# groundStation.net
KiCad netlist of a schematic drawn in EAGLE
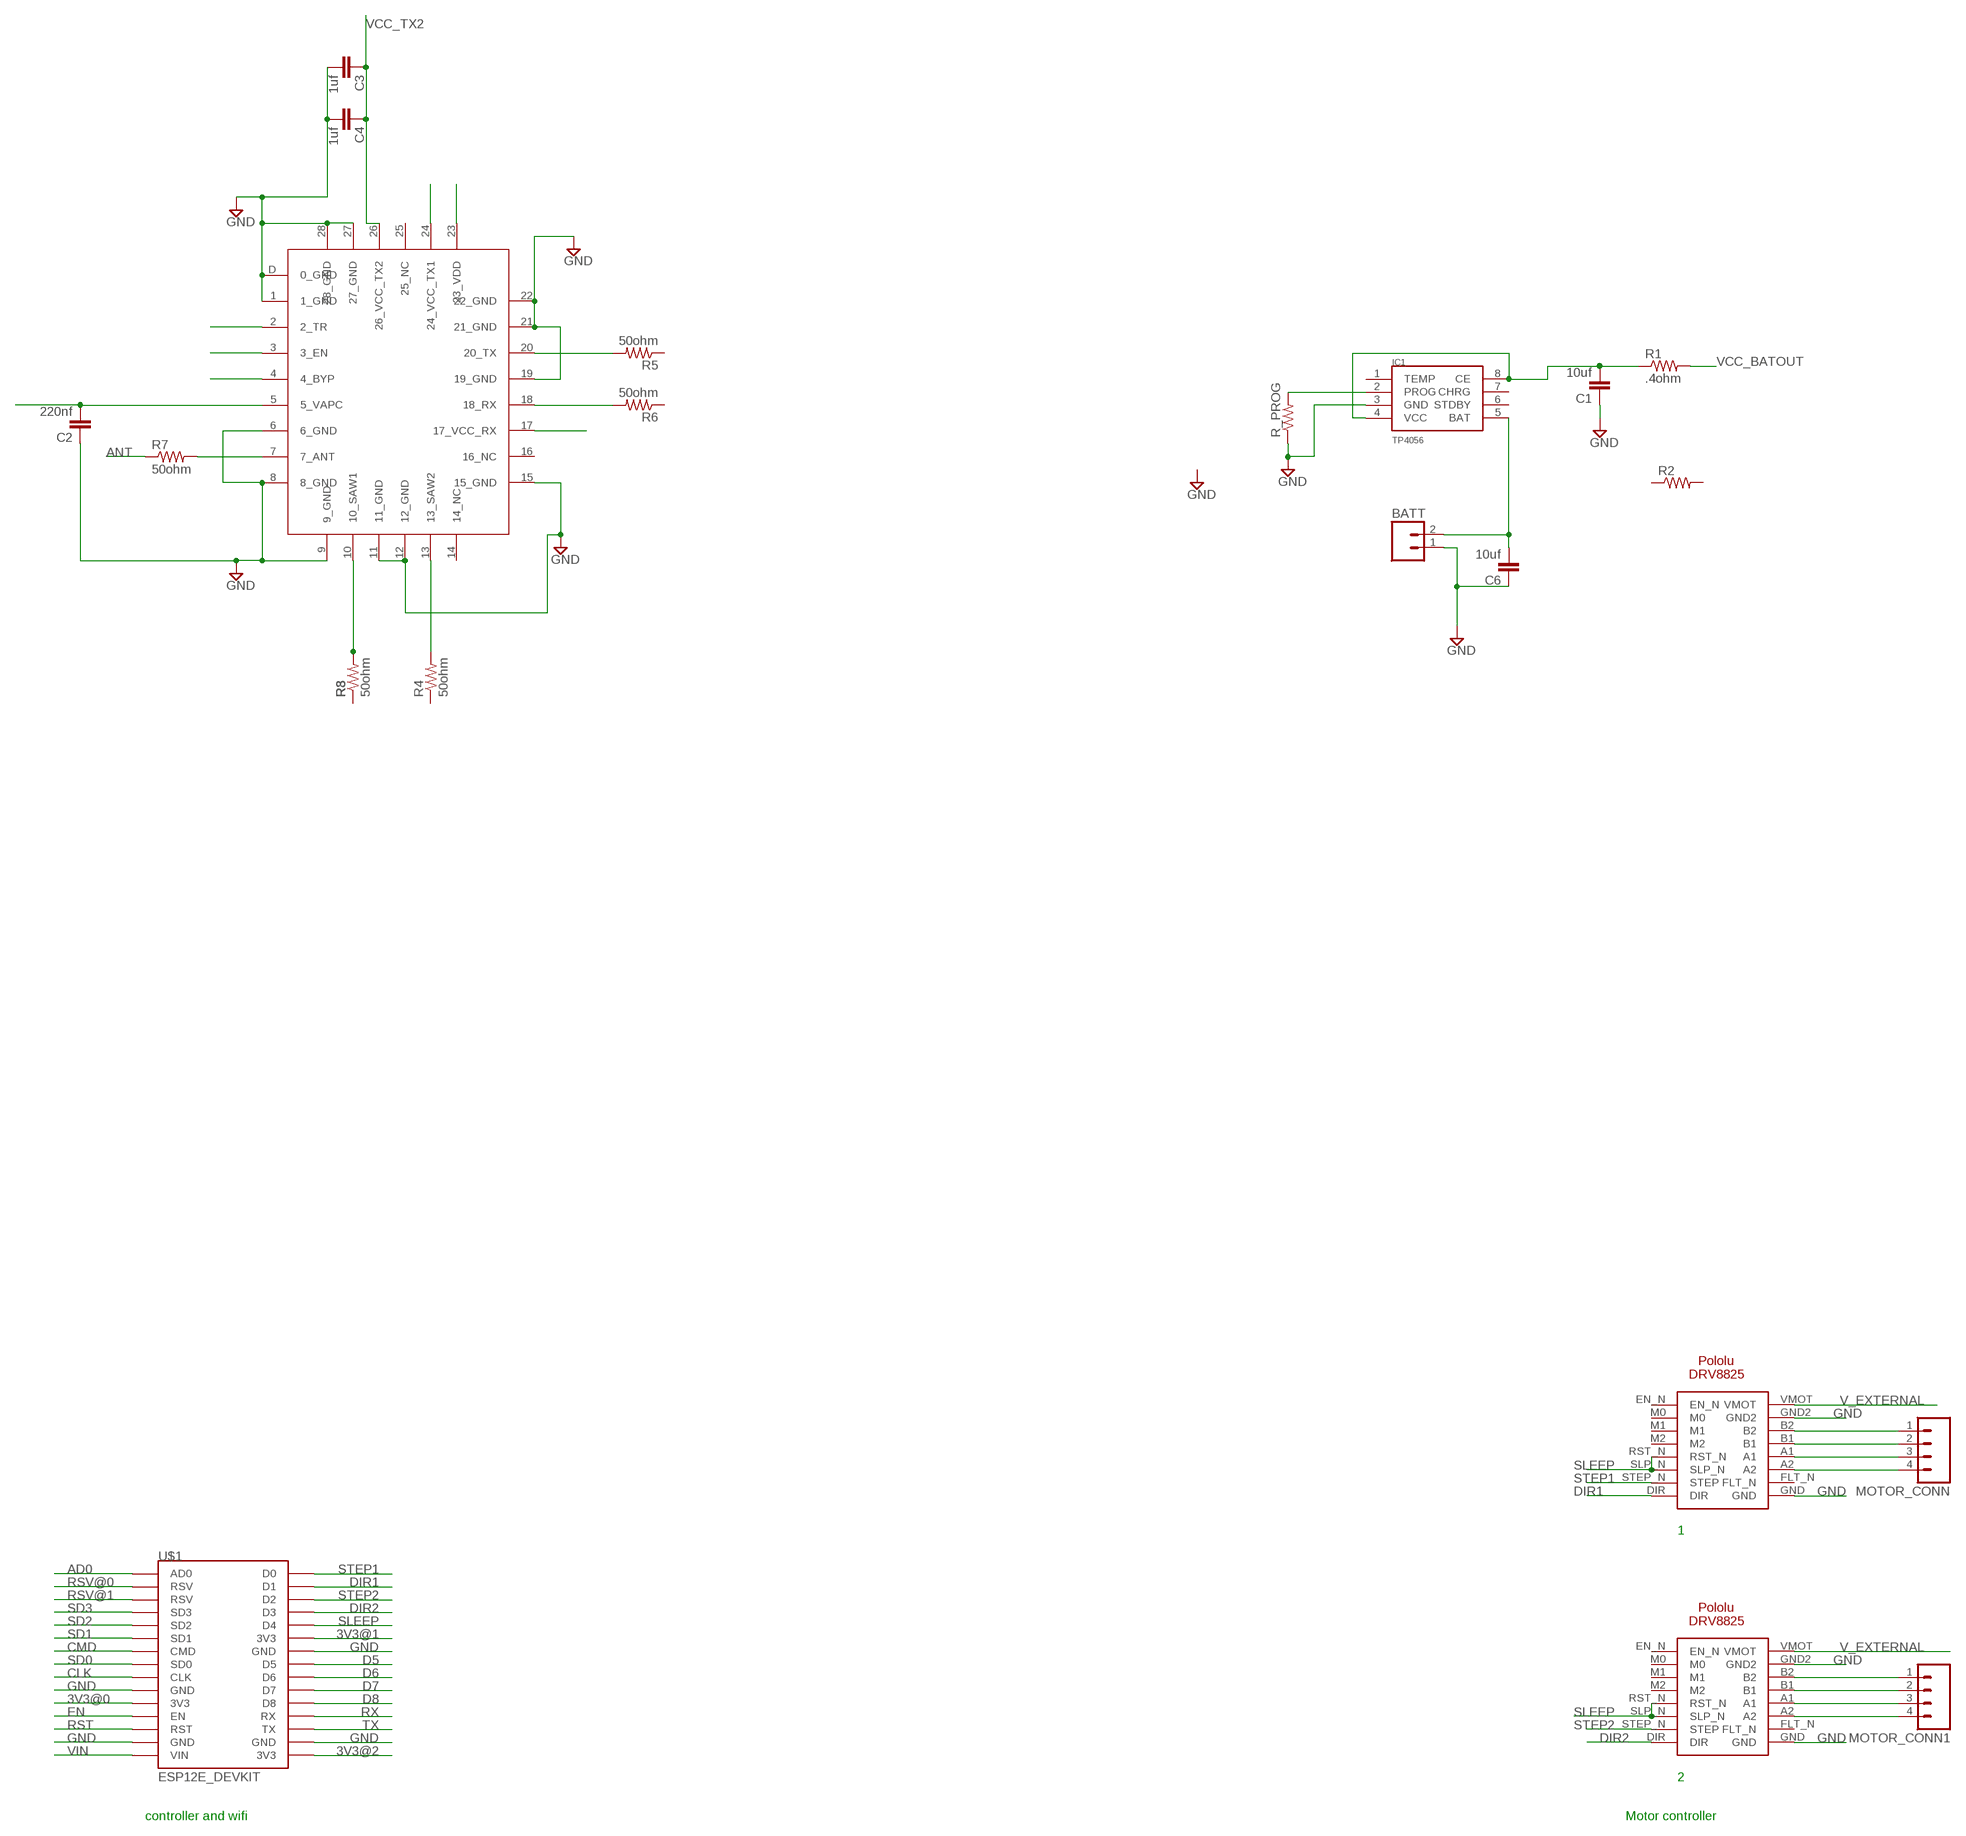
[diagram p0: schematic, sheet 1]

(export (version "E")
  (design (tool "Eeschema 10.0.6"))
  (components
    (comp (ref "BATT")
      (value "M02")
      (footprint "eagle-import:02P")
      (libsource (lib "eagle-import") (part "M02"))
    )
    (comp (ref "C1")
      (value "10uf")
      (footprint "eagle-import:0603")
      (libsource (lib "eagle-import") (part "0.1UF-0603-100V-10%"))
    )
    (comp (ref "C2")
      (value "220nf")
      (footprint "eagle-import:0603")
      (libsource (lib "eagle-import") (part "0.1UF-0603-100V-10%"))
    )
    (comp (ref "C3")
      (value "1uf")
      (footprint "eagle-import:0603")
      (libsource (lib "eagle-import") (part "0.1UF-0603-100V-10%"))
    )
    (comp (ref "C4")
      (value "1uf")
      (footprint "eagle-import:0603")
      (libsource (lib "eagle-import") (part "0.1UF-0603-100V-10%"))
    )
    (comp (ref "C6")
      (value "10uf")
      (footprint "eagle-import:0603")
      (libsource (lib "eagle-import") (part "0.1UF-0603-100V-10%"))
    )
    (comp (ref "IC1")
      (value "TP4056")
      (footprint "eagle-import:SOP-8")
      (libsource (lib "eagle-import") (part "TP4056"))
    )
    (comp (ref "MOTOR_CONN")
      (value "M04")
      (footprint "eagle-import:04P")
      (libsource (lib "eagle-import") (part "M04"))
    )
    (comp (ref "MOTOR_CONN1")
      (value "M04")
      (footprint "eagle-import:04P")
      (libsource (lib "eagle-import") (part "M04"))
    )
    (comp (ref "R1")
      (value ".4ohm")
      (footprint "eagle-import:R0603")
      (libsource (lib "eagle-import") (part "R-US_R0603"))
    )
    (comp (ref "R2")
      (value "R-US_R0603")
      (footprint "eagle-import:R0603")
      (libsource (lib "eagle-import") (part "R-US_R0603"))
    )
    (comp (ref "R3")
      (value "R-US_R0603")
      (footprint "eagle-import:R0603")
      (libsource (lib "eagle-import") (part "R-US_R0603"))
    )
    (comp (ref "R4")
      (value "50ohm")
      (footprint "eagle-import:R0603")
      (libsource (lib "eagle-import") (part "R-US_R0603"))
    )
    (comp (ref "R5")
      (value "50ohm")
      (footprint "eagle-import:R0603")
      (libsource (lib "eagle-import") (part "R-US_R0603"))
    )
    (comp (ref "R6")
      (value "50ohm")
      (footprint "eagle-import:R0603")
      (libsource (lib "eagle-import") (part "R-US_R0603"))
    )
    (comp (ref "R7")
      (value "50ohm")
      (footprint "eagle-import:R0603")
      (libsource (lib "eagle-import") (part "R-US_R0603"))
    )
    (comp (ref "R8")
      (value "50ohm")
      (footprint "eagle-import:R0603")
      (libsource (lib "eagle-import") (part "R-US_R0603"))
    )
    (comp (ref "R_PROG")
      (value "R-US_R0603")
      (footprint "eagle-import:R0603")
      (libsource (lib "eagle-import") (part "R-US_R0603"))
    )
    (comp (ref "U$1")
      (value "ESP12E_DEVKIT")
      (footprint "eagle-import:ESP12E_DEVKIT")
      (libsource (lib "eagle-import") (part "ESP12E_DEVKIT"))
    )
    (comp (ref "U$2")
      (value "POLOLU-DRV8825")
      (footprint "eagle-import:POLOLU-DRV8825")
      (libsource (lib "eagle-import") (part "POLOLU-DRV8825"))
    )
    (comp (ref "U$3")
      (value "RFFM6404")
      (footprint "eagle-import:RFFM6406")
      (libsource (lib "eagle-import") (part "RFFM6404"))
    )
    (comp (ref "U$4")
      (value "POLOLU-DRV8825")
      (footprint "eagle-import:POLOLU-DRV8825")
      (libsource (lib "eagle-import") (part "POLOLU-DRV8825"))
    )
  )
  (nets
    (net (code "1") (name "/3V3@0") (class "Default")
      (node (ref "U$1") (pin "3V3@0") (pinfunction "3V3_3V3@0") (pintype "bidirectional"))
    )
    (net (code "2") (name "/3V3@1") (class "Default")
      (node (ref "U$1") (pin "3V3@1") (pinfunction "3V3_3V3@1") (pintype "bidirectional"))
    )
    (net (code "3") (name "/3V3@2") (class "Default")
      (node (ref "U$1") (pin "3V3@2") (pinfunction "3V3_3V3@2") (pintype "bidirectional"))
    )
    (net (code "4") (name "/AD0") (class "Default")
      (node (ref "U$1") (pin "AD0") (pinfunction "AD0_AD0") (pintype "bidirectional"))
    )
    (net (code "5") (name "/ANT") (class "Default")
      (node (ref "R7") (pin "1") (pinfunction "1_1") (pintype "passive"))
    )
    (net (code "6") (name "/CLK") (class "Default")
      (node (ref "U$1") (pin "CLK") (pinfunction "CLK_CLK") (pintype "bidirectional"))
    )
    (net (code "7") (name "/CMD") (class "Default")
      (node (ref "U$1") (pin "CMD") (pinfunction "CMD_CMD") (pintype "bidirectional"))
    )
    (net (code "8") (name "/D5") (class "Default")
      (node (ref "U$1") (pin "D5") (pinfunction "D5_D5") (pintype "bidirectional"))
    )
    (net (code "9") (name "/D6") (class "Default")
      (node (ref "U$1") (pin "D6") (pinfunction "D6_D6") (pintype "bidirectional"))
    )
    (net (code "10") (name "/D7") (class "Default")
      (node (ref "U$1") (pin "D7") (pinfunction "D7_D7") (pintype "bidirectional"))
    )
    (net (code "11") (name "/D8") (class "Default")
      (node (ref "U$1") (pin "D8") (pinfunction "D8_D8") (pintype "bidirectional"))
    )
    (net (code "12") (name "/DIR1") (class "Default")
      (node (ref "U$1") (pin "D1") (pinfunction "D1_D1") (pintype "bidirectional"))
      (node (ref "U$2") (pin "DIR") (pinfunction "DIR_DIR") (pintype "bidirectional"))
    )
    (net (code "13") (name "/DIR2") (class "Default")
      (node (ref "U$1") (pin "D3") (pinfunction "D3_D3") (pintype "bidirectional"))
      (node (ref "U$4") (pin "DIR") (pinfunction "DIR_DIR") (pintype "bidirectional"))
    )
    (net (code "14") (name "/EN") (class "Default")
      (node (ref "U$1") (pin "EN") (pinfunction "EN_EN") (pintype "bidirectional"))
    )
    (net (code "15") (name "/RST") (class "Default")
      (node (ref "U$1") (pin "RST") (pinfunction "RST_RST") (pintype "bidirectional"))
    )
    (net (code "16") (name "/RSV@0") (class "Default")
      (node (ref "U$1") (pin "RSV@0") (pinfunction "RSV_RSV@0") (pintype "bidirectional"))
    )
    (net (code "17") (name "/RSV@1") (class "Default")
      (node (ref "U$1") (pin "RSV@1") (pinfunction "RSV_RSV@1") (pintype "bidirectional"))
    )
    (net (code "18") (name "/RX") (class "Default")
      (node (ref "U$1") (pin "RX") (pinfunction "RX_RX") (pintype "bidirectional"))
    )
    (net (code "19") (name "/SD0") (class "Default")
      (node (ref "U$1") (pin "SD0") (pinfunction "SD0_SD0") (pintype "bidirectional"))
    )
    (net (code "20") (name "/SD1") (class "Default")
      (node (ref "U$1") (pin "SD1") (pinfunction "SD1_SD1") (pintype "bidirectional"))
    )
    (net (code "21") (name "/SD2") (class "Default")
      (node (ref "U$1") (pin "SD2") (pinfunction "SD2_SD2") (pintype "bidirectional"))
    )
    (net (code "22") (name "/SD3") (class "Default")
      (node (ref "U$1") (pin "SD3") (pinfunction "SD3_SD3") (pintype "bidirectional"))
    )
    (net (code "23") (name "/SLEEP") (class "Default")
      (node (ref "U$1") (pin "D4") (pinfunction "D4_D4") (pintype "bidirectional"))
      (node (ref "U$2") (pin "RST_N") (pinfunction "RST_N_RST_N") (pintype "bidirectional"))
      (node (ref "U$2") (pin "SLP_N") (pinfunction "SLP_N_SLP_N") (pintype "bidirectional"))
      (node (ref "U$4") (pin "RST_N") (pinfunction "RST_N_RST_N") (pintype "bidirectional"))
      (node (ref "U$4") (pin "SLP_N") (pinfunction "SLP_N_SLP_N") (pintype "bidirectional"))
    )
    (net (code "24") (name "/STEP1") (class "Default")
      (node (ref "U$1") (pin "D0") (pinfunction "D0_D0") (pintype "bidirectional"))
      (node (ref "U$2") (pin "STEP_N") (pinfunction "STEP_STEP_N") (pintype "bidirectional"))
    )
    (net (code "25") (name "/STEP2") (class "Default")
      (node (ref "U$1") (pin "D2") (pinfunction "D2_D2") (pintype "bidirectional"))
      (node (ref "U$4") (pin "STEP_N") (pinfunction "STEP_STEP_N") (pintype "bidirectional"))
    )
    (net (code "26") (name "/TX") (class "Default")
      (node (ref "U$1") (pin "TX") (pinfunction "TX_TX") (pintype "bidirectional"))
    )
    (net (code "27") (name "/VCC_BATOUT") (class "Default")
      (node (ref "R1") (pin "2") (pinfunction "2_2") (pintype "passive"))
    )
    (net (code "28") (name "/VCC_TX2") (class "Default")
      (node (ref "C3") (pin "1") (pinfunction "1_1") (pintype "passive"))
      (node (ref "C4") (pin "1") (pinfunction "1_1") (pintype "passive"))
      (node (ref "U$3") (pin "26") (pinfunction "26_VCC_TX2_26") (pintype "bidirectional"))
    )
    (net (code "29") (name "/VIN") (class "Default")
      (node (ref "U$1") (pin "VIN") (pinfunction "VIN_VIN") (pintype "bidirectional"))
    )
    (net (code "30") (name "/V_EXTERNAL") (class "Default")
      (node (ref "U$2") (pin "VMOT") (pinfunction "VMOT_VMOT") (pintype "bidirectional"))
      (node (ref "U$4") (pin "VMOT") (pinfunction "VMOT_VMOT") (pintype "bidirectional"))
    )
    (net (code "31") (name "GND") (class "Default")
      (node (ref "BATT") (pin "1") (pinfunction "1_1") (pintype "passive"))
      (node (ref "C1") (pin "1") (pinfunction "1_1") (pintype "passive"))
      (node (ref "C2") (pin "1") (pinfunction "1_1") (pintype "passive"))
      (node (ref "C3") (pin "2") (pinfunction "2_2") (pintype "passive"))
      (node (ref "C4") (pin "2") (pinfunction "2_2") (pintype "passive"))
      (node (ref "C6") (pin "1") (pinfunction "1_1") (pintype "passive"))
      (node (ref "IC1") (pin "3") (pinfunction "GND_3") (pintype "bidirectional"))
      (node (ref "R_PROG") (pin "1") (pinfunction "1_1") (pintype "passive"))
      (node (ref "U$1") (pin "GND@0") (pinfunction "GND_GND@0") (pintype "bidirectional"))
      (node (ref "U$1") (pin "GND@1") (pinfunction "GND_GND@1") (pintype "bidirectional"))
      (node (ref "U$1") (pin "GND@2") (pinfunction "GND_GND@2") (pintype "bidirectional"))
      (node (ref "U$1") (pin "GND@3") (pinfunction "GND_GND@3") (pintype "bidirectional"))
      (node (ref "U$2") (pin "GND") (pinfunction "GND_GND") (pintype "bidirectional"))
      (node (ref "U$2") (pin "GND2") (pinfunction "GND2_GND2") (pintype "bidirectional"))
      (node (ref "U$3") (pin "1") (pinfunction "1_GND_1") (pintype "bidirectional"))
      (node (ref "U$3") (pin "11") (pinfunction "11_GND_11") (pintype "bidirectional"))
      (node (ref "U$3") (pin "12") (pinfunction "12_GND_12") (pintype "bidirectional"))
      (node (ref "U$3") (pin "15") (pinfunction "15_GND_15") (pintype "bidirectional"))
      (node (ref "U$3") (pin "19") (pinfunction "19_GND_19") (pintype "bidirectional"))
      (node (ref "U$3") (pin "21") (pinfunction "21_GND_21") (pintype "bidirectional"))
      (node (ref "U$3") (pin "22") (pinfunction "22_GND_22") (pintype "bidirectional"))
      (node (ref "U$3") (pin "27") (pinfunction "27_GND_27") (pintype "bidirectional"))
      (node (ref "U$3") (pin "28") (pinfunction "28_GND_28") (pintype "bidirectional"))
      (node (ref "U$3") (pin "6") (pinfunction "6_GND_6") (pintype "bidirectional"))
      (node (ref "U$3") (pin "8") (pinfunction "8_GND_8") (pintype "bidirectional"))
      (node (ref "U$3") (pin "9") (pinfunction "9_GND_9") (pintype "bidirectional"))
      (node (ref "U$3") (pin "D") (pinfunction "0_GND_D") (pintype "bidirectional"))
      (node (ref "U$4") (pin "GND") (pinfunction "GND_GND") (pintype "bidirectional"))
      (node (ref "U$4") (pin "GND2") (pinfunction "GND2_GND2") (pintype "bidirectional"))
    )
    (net (code "32") (name "Net-(IC1-BAT)") (class "Default")
      (node (ref "BATT") (pin "2") (pinfunction "2_2") (pintype "passive"))
      (node (ref "C6") (pin "2") (pinfunction "2_2") (pintype "passive"))
      (node (ref "IC1") (pin "5") (pinfunction "BAT_5") (pintype "bidirectional"))
    )
    (net (code "33") (name "Net-(IC1-CE)") (class "Default")
      (node (ref "C1") (pin "2") (pinfunction "2_2") (pintype "passive"))
      (node (ref "IC1") (pin "4") (pinfunction "VCC_4") (pintype "bidirectional"))
      (node (ref "IC1") (pin "8") (pinfunction "CE_8") (pintype "bidirectional"))
      (node (ref "R1") (pin "1") (pinfunction "1_1") (pintype "passive"))
    )
    (net (code "34") (name "Net-(IC1-PROG)") (class "Default")
      (node (ref "IC1") (pin "2") (pinfunction "PROG_2") (pintype "bidirectional"))
      (node (ref "R_PROG") (pin "2") (pinfunction "2_2") (pintype "passive"))
    )
    (net (code "35") (name "Net-(MOTOR_CONN-Pad1)") (class "Default")
      (node (ref "MOTOR_CONN") (pin "1") (pinfunction "1_1") (pintype "passive"))
      (node (ref "U$2") (pin "B2") (pinfunction "B2_B2") (pintype "bidirectional"))
    )
    (net (code "36") (name "Net-(MOTOR_CONN-Pad2)") (class "Default")
      (node (ref "MOTOR_CONN") (pin "2") (pinfunction "2_2") (pintype "passive"))
      (node (ref "U$2") (pin "B1") (pinfunction "B1_B1") (pintype "bidirectional"))
    )
    (net (code "37") (name "Net-(MOTOR_CONN-Pad3)") (class "Default")
      (node (ref "MOTOR_CONN") (pin "3") (pinfunction "3_3") (pintype "passive"))
      (node (ref "U$2") (pin "A1") (pinfunction "A1_A1") (pintype "bidirectional"))
    )
    (net (code "38") (name "Net-(MOTOR_CONN-Pad4)") (class "Default")
      (node (ref "MOTOR_CONN") (pin "4") (pinfunction "4_4") (pintype "passive"))
      (node (ref "U$2") (pin "A2") (pinfunction "A2_A2") (pintype "bidirectional"))
    )
    (net (code "39") (name "Net-(MOTOR_CONN1-Pad1)") (class "Default")
      (node (ref "MOTOR_CONN1") (pin "1") (pinfunction "1_1") (pintype "passive"))
      (node (ref "U$4") (pin "B2") (pinfunction "B2_B2") (pintype "bidirectional"))
    )
    (net (code "40") (name "Net-(MOTOR_CONN1-Pad2)") (class "Default")
      (node (ref "MOTOR_CONN1") (pin "2") (pinfunction "2_2") (pintype "passive"))
      (node (ref "U$4") (pin "B1") (pinfunction "B1_B1") (pintype "bidirectional"))
    )
    (net (code "41") (name "Net-(MOTOR_CONN1-Pad3)") (class "Default")
      (node (ref "MOTOR_CONN1") (pin "3") (pinfunction "3_3") (pintype "passive"))
      (node (ref "U$4") (pin "A1") (pinfunction "A1_A1") (pintype "bidirectional"))
    )
    (net (code "42") (name "Net-(MOTOR_CONN1-Pad4)") (class "Default")
      (node (ref "MOTOR_CONN1") (pin "4") (pinfunction "4_4") (pintype "passive"))
      (node (ref "U$4") (pin "A2") (pinfunction "A2_A2") (pintype "bidirectional"))
    )
    (net (code "43") (name "Net-(R3-Pad1)") (class "Default")
      (node (ref "R3") (pin "1") (pinfunction "1_1") (pintype "passive"))
      (node (ref "R8") (pin "1") (pinfunction "1_1") (pintype "passive"))
    )
    (net (code "44") (name "Net-(U$3-5_VAPC)") (class "Default")
      (node (ref "C2") (pin "2") (pinfunction "2_2") (pintype "passive"))
      (node (ref "U$3") (pin "5") (pinfunction "5_VAPC_5") (pintype "bidirectional"))
    )
    (net (code "45") (name "Net-(U$3-7_ANT)") (class "Default")
      (node (ref "R7") (pin "2") (pinfunction "2_2") (pintype "passive"))
      (node (ref "U$3") (pin "7") (pinfunction "7_ANT_7") (pintype "bidirectional"))
    )
    (net (code "46") (name "Net-(U$3-10_SAW1)") (class "Default")
      (node (ref "R3") (pin "2") (pinfunction "2_2") (pintype "passive"))
      (node (ref "R8") (pin "2") (pinfunction "2_2") (pintype "passive"))
      (node (ref "U$3") (pin "10") (pinfunction "10_SAW1_10") (pintype "bidirectional"))
    )
    (net (code "47") (name "Net-(U$3-13_SAW2)") (class "Default")
      (node (ref "R4") (pin "2") (pinfunction "2_2") (pintype "passive"))
      (node (ref "U$3") (pin "13") (pinfunction "13_SAW2_13") (pintype "bidirectional"))
    )
    (net (code "48") (name "Net-(U$3-18_RX)") (class "Default")
      (node (ref "R6") (pin "2") (pinfunction "2_2") (pintype "passive"))
      (node (ref "U$3") (pin "18") (pinfunction "18_RX_18") (pintype "bidirectional"))
    )
    (net (code "49") (name "Net-(U$3-20_TX)") (class "Default")
      (node (ref "R5") (pin "2") (pinfunction "2_2") (pintype "passive"))
      (node (ref "U$3") (pin "20") (pinfunction "20_TX_20") (pintype "bidirectional"))
    )
    (net (code "50") (name "unconnected-(IC1-CHRG-Pad7)") (class "Default")
      (node (ref "IC1") (pin "7") (pinfunction "CHRG_7") (pintype "bidirectional"))
    )
    (net (code "51") (name "unconnected-(IC1-STDBY-Pad6)") (class "Default")
      (node (ref "IC1") (pin "6") (pinfunction "STDBY_6") (pintype "bidirectional"))
    )
    (net (code "52") (name "unconnected-(IC1-TEMP-Pad1)") (class "Default")
      (node (ref "IC1") (pin "1") (pinfunction "TEMP_1") (pintype "bidirectional"))
    )
    (net (code "53") (name "unconnected-(R2-Pad1)") (class "Default")
      (node (ref "R2") (pin "1") (pinfunction "1_1") (pintype "passive"))
    )
    (net (code "54") (name "unconnected-(R2-Pad2)") (class "Default")
      (node (ref "R2") (pin "2") (pinfunction "2_2") (pintype "passive"))
    )
    (net (code "55") (name "unconnected-(R4-Pad1)") (class "Default")
      (node (ref "R4") (pin "1") (pinfunction "1_1") (pintype "passive"))
    )
    (net (code "56") (name "unconnected-(R5-Pad1)") (class "Default")
      (node (ref "R5") (pin "1") (pinfunction "1_1") (pintype "passive"))
    )
    (net (code "57") (name "unconnected-(R6-Pad1)") (class "Default")
      (node (ref "R6") (pin "1") (pinfunction "1_1") (pintype "passive"))
    )
    (net (code "58") (name "unconnected-(U$2-PadEN_N)") (class "Default")
      (node (ref "U$2") (pin "EN_N") (pinfunction "EN_N_EN_N") (pintype "bidirectional"))
    )
    (net (code "59") (name "unconnected-(U$2-PadFLT_N)") (class "Default")
      (node (ref "U$2") (pin "FLT_N") (pinfunction "FLT_N_FLT_N") (pintype "bidirectional"))
    )
    (net (code "60") (name "unconnected-(U$2-PadM0)") (class "Default")
      (node (ref "U$2") (pin "M0") (pinfunction "M0_M0") (pintype "bidirectional"))
    )
    (net (code "61") (name "unconnected-(U$2-PadM1)") (class "Default")
      (node (ref "U$2") (pin "M1") (pinfunction "M1_M1") (pintype "bidirectional"))
    )
    (net (code "62") (name "unconnected-(U$2-PadM2)") (class "Default")
      (node (ref "U$2") (pin "M2") (pinfunction "M2_M2") (pintype "bidirectional"))
    )
    (net (code "63") (name "unconnected-(U$3-2_TR-Pad2)") (class "Default")
      (node (ref "U$3") (pin "2") (pinfunction "2_TR_2") (pintype "bidirectional"))
    )
    (net (code "64") (name "unconnected-(U$3-3_EN-Pad3)") (class "Default")
      (node (ref "U$3") (pin "3") (pinfunction "3_EN_3") (pintype "bidirectional"))
    )
    (net (code "65") (name "unconnected-(U$3-4_BYP-Pad4)") (class "Default")
      (node (ref "U$3") (pin "4") (pinfunction "4_BYP_4") (pintype "bidirectional"))
    )
    (net (code "66") (name "unconnected-(U$3-14_NC-Pad14)") (class "Default")
      (node (ref "U$3") (pin "14") (pinfunction "14_NC_14") (pintype "bidirectional"))
    )
    (net (code "67") (name "unconnected-(U$3-16_NC-Pad16)") (class "Default")
      (node (ref "U$3") (pin "16") (pinfunction "16_NC_16") (pintype "bidirectional"))
    )
    (net (code "68") (name "unconnected-(U$3-17_VCC_RX-Pad17)") (class "Default")
      (node (ref "U$3") (pin "17") (pinfunction "17_VCC_RX_17") (pintype "bidirectional"))
    )
    (net (code "69") (name "unconnected-(U$3-23_VDD-Pad23)") (class "Default")
      (node (ref "U$3") (pin "23") (pinfunction "23_VDD_23") (pintype "bidirectional"))
    )
    (net (code "70") (name "unconnected-(U$3-24_VCC_TX1-Pad24)") (class "Default")
      (node (ref "U$3") (pin "24") (pinfunction "24_VCC_TX1_24") (pintype "bidirectional"))
    )
    (net (code "71") (name "unconnected-(U$3-25_NC-Pad25)") (class "Default")
      (node (ref "U$3") (pin "25") (pinfunction "25_NC_25") (pintype "bidirectional"))
    )
    (net (code "72") (name "unconnected-(U$4-PadEN_N)") (class "Default")
      (node (ref "U$4") (pin "EN_N") (pinfunction "EN_N_EN_N") (pintype "bidirectional"))
    )
    (net (code "73") (name "unconnected-(U$4-PadFLT_N)") (class "Default")
      (node (ref "U$4") (pin "FLT_N") (pinfunction "FLT_N_FLT_N") (pintype "bidirectional"))
    )
    (net (code "74") (name "unconnected-(U$4-PadM0)") (class "Default")
      (node (ref "U$4") (pin "M0") (pinfunction "M0_M0") (pintype "bidirectional"))
    )
    (net (code "75") (name "unconnected-(U$4-PadM1)") (class "Default")
      (node (ref "U$4") (pin "M1") (pinfunction "M1_M1") (pintype "bidirectional"))
    )
    (net (code "76") (name "unconnected-(U$4-PadM2)") (class "Default")
      (node (ref "U$4") (pin "M2") (pinfunction "M2_M2") (pintype "bidirectional"))
    )
  )
)
